# MIDI.net
KiCad netlist of a schematic drawn in Altium Designer
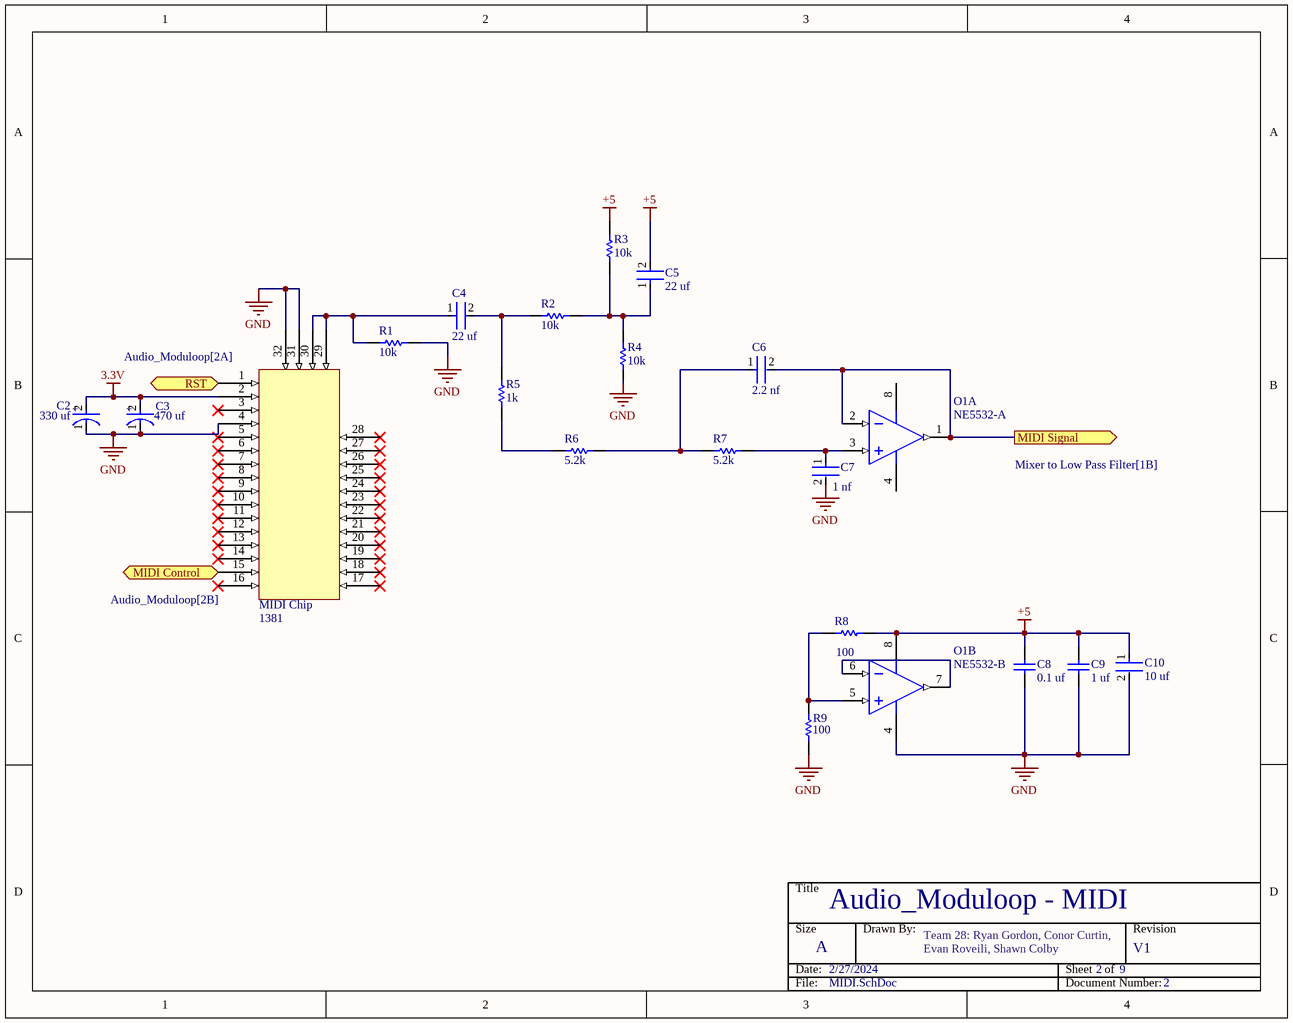
[diagram p0: MIDI.SchDoc]

(export (version "E")
  (design (tool "Eeschema 10.0.6"))
  (components
    (comp (ref "C2")
      (value "330 uf")
      (footprint "FP-RAD-TH-D_6_3_0_5-L_11-MFG")
      (description "Aluminum Electrolytic Capacitors (Radial Lead Type) 330uF ±20% 6.3V")
      (fields (field (name "TOLERANCE") "20%"))
      (libsource (lib "Altium Content Vault") (part "a00bbbee19879c290e62620ae7e47b1"))
    )
    (comp (ref "C3")
      (value "470 uf")
      (footprint "FP-RAD-TH-D_10_0_5-L_16_1-MFG")
      (description "Aluminum Electrolytic Capacitors (Radial Lead Type) AEC-Q200 Qualified 470uF ±20% 25V")
      (fields (field (name "TOLERANCE") "20%") (field (name "VOLTAGE") "25V"))
      (libsource (lib "Altium Content Vault") (part "a00bbbee19879c290e62620ae7e47b1"))
    )
    (comp (ref "C4")
      (value "22 uf")
      (footprint "FP-RCEWM1-MFG")
      (description "CAP CER 22UF 25V X7R RADIAL")
      (fields (field (name "TOLERANCE") "20%"))
      (libsource (lib "Altium Content Vault") (part "02cd4be3c70576c341d710602a673aa"))
    )
    (comp (ref "C5")
      (value "22 uf")
      (footprint "FP-RCEWM1-MFG")
      (description "CAP CER 22UF 25V X7R RADIAL")
      (fields (field (name "TOLERANCE") "20%"))
      (libsource (lib "Altium Content Vault") (part "02cd4be3c70576c341d710602a673aa"))
    )
    (comp (ref "C6")
      (value "2.2 nf")
      (footprint "FP-RCE0DB-MFG")
      (description "Cap Ceramic 1nF 50V X7R ±10% Radial 2.5mm +125°C Ammo Pack")
      (fields (field (name "TOLERANCE") "10%"))
      (libsource (lib "Altium Content Vault") (part "b4654b650e69147ec39a6b967a45e02"))
    )
    (comp (ref "C7")
      (value "1 nf")
      (footprint "FP-RCE0DB-MFG")
      (description "Cap Ceramic 470pF 100V X7R ±10% Radial 2.5mm +125°C Ammo Pack")
      (fields (field (name "TOLERANCE") "10%"))
      (libsource (lib "Altium Content Vault") (part "b4654b650e69147ec39a6b967a45e02"))
    )
    (comp (ref "C8")
      (value "0.1 uf")
      (footprint "CAPC2013X135X45ML10T25")
      (description "Chip Capacitor, 0.1 uF, +/- 10%, 50 V, -55 to 125 degC, 0805 (2012 Metric), RoHS, Tape and Reel")
      (fields (field (name "VOLTAGE") "50V") (field (name "TOLERANCE") "10%"))
      (libsource (lib "Altium Content Vault") (part "CAP-NP-2"))
    )
    (comp (ref "C9")
      (value "1 uf")
      (footprint "CAPC2013X145X50LL20T25")
      (fields (field (name "MANUFACTURER") "Kemet") (field (name "PART NUMBER") "C0805C105K4PACTU"))
      (libsource (lib "Altium Content Vault") (part "CAP"))
    )
    (comp (ref "C10")
      (value "10 uf")
      (footprint "FP-C0805C-DG-MFG")
      (description "CAP CER 10UF 10V X5R 0805")
      (fields (field (name "TOLERANCE") "10%") (field (name "MANUFACTURER PART NUMBER") "C0805C106K8PACTU"))
      (libsource (lib "Altium Content Vault") (part "11868f565c42a9108669ba33697ecf6"))
    )
    (comp (ref "MIDI Chip")
      (value "1381")
      (footprint "FEATHERWING")
      (description "Conn, Rect, PowerPoleHousing, PP180Series, Blue, 180A, 600V")
      (libsource (lib "Ryamgordon") (part "1381"))
    )
    (comp (ref "O1")
      (value "NE5532-A")
      (footprint "ONSC-SOIC-8-751-07_V")
      (fields (field (name "MANUFACTURER") "On Semiconductor") (field (name "PARTNUMBER") "NE5532AD8R2G"))
      (libsource (lib "Altium Content Vault") (part "ONSC-NE5532-SOIC-8-751-07"))
    )
    (comp (ref "R1")
      (value "10k")
      (footprint "RESC2013X60X35NL10T20")
      (description "Chip Resistor, 10 KOhm, +/- 1%, 0.125 W, -55 to 155 degC, 0805 (2012 Metric), RoHS, Tape and Reel")
      (fields (field (name "MANUFACTURER") "Yageo"))
      (libsource (lib "Altium Content Vault") (part "RES-2"))
    )
    (comp (ref "R2")
      (value "10k")
      (footprint "RESC2013X60X35NL10T20")
      (description "Chip Resistor, 10 KOhm, +/- 1%, 0.125 W, -55 to 155 degC, 0805 (2012 Metric), RoHS, Tape and Reel")
      (fields (field (name "MANUFACTURER") "Yageo"))
      (libsource (lib "Altium Content Vault") (part "RES-2"))
    )
    (comp (ref "R3")
      (value "10k")
      (footprint "RESC2013X60X35NL10T20")
      (description "Chip Resistor, 10 KOhm, +/- 1%, 0.125 W, -55 to 155 degC, 0805 (2012 Metric), RoHS, Tape and Reel")
      (fields (field (name "MANUFACTURER") "Yageo"))
      (libsource (lib "Altium Content Vault") (part "RES-2"))
    )
    (comp (ref "R4")
      (value "10k")
      (footprint "RESC2013X60X35NL10T20")
      (description "Chip Resistor, 10 KOhm, +/- 1%, 0.125 W, -55 to 155 degC, 0805 (2012 Metric), RoHS, Tape and Reel")
      (fields (field (name "MANUFACTURER") "Yageo"))
      (libsource (lib "Altium Content Vault") (part "RES-2"))
    )
    (comp (ref "R5")
      (value "1k")
      (footprint "RESC2013X60X40LL20T25")
      (fields (field (name "MANUFACTURER") "Panasonic") (field (name "PART NUMBER") "ERA6AEB152V"))
      (libsource (lib "Altium Content Vault") (part "RES"))
    )
    (comp (ref "R6")
      (value "5.2k")
      (footprint "RESC2013X70X40LL20T20")
      (fields (field (name "MANUFACTURER") "Panasonic") (field (name "PART NUMBER") "ERJ6ENF6801V"))
      (libsource (lib "Altium Content Vault") (part "RES"))
    )
    (comp (ref "R7")
      (value "5.2k")
      (footprint "RESC2013X70X40LL20T20")
      (fields (field (name "MANUFACTURER") "Panasonic") (field (name "PART NUMBER") "ERJ6ENF6801V"))
      (libsource (lib "Altium Content Vault") (part "RES"))
    )
    (comp (ref "R8")
      (value "100")
      (footprint "RESC2013X60X40ML20T25")
      (fields (field (name "MANUFACTURER") "Panasonic") (field (name "PART NUMBER") "ERA6AEB101V"))
      (libsource (lib "Altium Content Vault") (part "RES"))
    )
    (comp (ref "R9")
      (value "100")
      (footprint "RESC2013X60X40ML20T25")
      (fields (field (name "MANUFACTURER") "Panasonic") (field (name "PART NUMBER") "ERA6AEB101V"))
      (libsource (lib "Altium Content Vault") (part "RES"))
    )
  )
  (nets
    (net (code "1") (name "+5") (class "Default")
      (node (ref "C10") (pin "1") (pinfunction "1_1") (pintype "passive"))
      (node (ref "C5") (pin "2") (pinfunction "2_2") (pintype "passive"))
      (node (ref "C8") (pin "1") (pinfunction "1_1") (pintype "passive"))
      (node (ref "C9") (pin "1") (pinfunction "1_1") (pintype "passive"))
      (node (ref "O1") (pin "8") (pinfunction "V+_8") (pintype "power_in"))
      (node (ref "R3") (pin "1") (pinfunction "1_1") (pintype "passive"))
      (node (ref "R8") (pin "2") (pinfunction "2_2") (pintype "passive"))
    )
    (net (code "2") (name "/MIDI Control") (class "Default")
      (node (ref "MIDI Chip") (pin "15") (pintype "input"))
    )
    (net (code "3") (name "/MIDI Signal") (class "Default")
      (node (ref "C6") (pin "2") (pinfunction "2_2") (pintype "passive"))
      (node (ref "O1") (pin "1") (pinfunction "OUTA_1") (pintype "output"))
      (node (ref "O1") (pin "2") (pinfunction "INA-_2") (pintype "input"))
    )
    (net (code "4") (name "/RST") (class "Default") (node (ref "MIDI Chip") (pin "1") (pintype "input")))
    (net (code "5") (name "3.3V") (class "Default")
      (node (ref "C2") (pin "2") (pinfunction "A_2") (pintype "passive"))
      (node (ref "C3") (pin "2") (pinfunction "A_2") (pintype "passive"))
      (node (ref "MIDI Chip") (pin "2") (pintype "input"))
    )
    (net (code "6") (name "GND") (class "Default")
      (node (ref "C10") (pin "2") (pinfunction "2_2") (pintype "passive"))
      (node (ref "C2") (pin "1") (pinfunction "C_1") (pintype "passive"))
      (node (ref "C3") (pin "1") (pinfunction "C_1") (pintype "passive"))
      (node (ref "C7") (pin "2") (pinfunction "2_2") (pintype "passive"))
      (node (ref "C8") (pin "2") (pinfunction "2_2") (pintype "passive"))
      (node (ref "C9") (pin "2") (pinfunction "2_2") (pintype "passive"))
      (node (ref "MIDI Chip") (pin "31") (pintype "input"))
      (node (ref "MIDI Chip") (pin "32") (pintype "input"))
      (node (ref "MIDI Chip") (pin "4") (pintype "input"))
      (node (ref "O1") (pin "4") (pinfunction "V-_4") (pintype "power_in"))
      (node (ref "R1") (pin "2") (pinfunction "2_2") (pintype "passive"))
      (node (ref "R4") (pin "2") (pinfunction "2_2") (pintype "passive"))
      (node (ref "R9") (pin "1") (pinfunction "1_1") (pintype "passive"))
    )
    (net (code "7") (name "Net-(C4-Pad1)") (class "Default")
      (node (ref "C4") (pin "1") (pinfunction "1_1") (pintype "passive"))
      (node (ref "MIDI Chip") (pin "29") (pintype "input"))
      (node (ref "MIDI Chip") (pin "30") (pintype "input"))
      (node (ref "R1") (pin "1") (pinfunction "1_1") (pintype "passive"))
    )
    (net (code "8") (name "Net-(C4-Pad2)") (class "Default")
      (node (ref "C4") (pin "2") (pinfunction "2_2") (pintype "passive"))
      (node (ref "R2") (pin "1") (pinfunction "1_1") (pintype "passive"))
      (node (ref "R5") (pin "2") (pinfunction "2_2") (pintype "passive"))
    )
    (net (code "9") (name "Net-(C5-Pad1)") (class "Default")
      (node (ref "C5") (pin "1") (pinfunction "1_1") (pintype "passive"))
      (node (ref "R2") (pin "2") (pinfunction "2_2") (pintype "passive"))
      (node (ref "R3") (pin "2") (pinfunction "2_2") (pintype "passive"))
      (node (ref "R4") (pin "1") (pinfunction "1_1") (pintype "passive"))
    )
    (net (code "10") (name "Net-(C6-Pad1)") (class "Default")
      (node (ref "C6") (pin "1") (pinfunction "1_1") (pintype "passive"))
      (node (ref "R6") (pin "2") (pinfunction "2_2") (pintype "passive"))
      (node (ref "R7") (pin "1") (pinfunction "1_1") (pintype "passive"))
    )
    (net (code "11") (name "Net-(O1A-INA+)") (class "Default")
      (node (ref "C7") (pin "1") (pinfunction "1_1") (pintype "passive"))
      (node (ref "O1") (pin "3") (pinfunction "INA+_3") (pintype "input"))
      (node (ref "R7") (pin "2") (pinfunction "2_2") (pintype "passive"))
    )
    (net (code "12") (name "Net-(O1B-INB+)") (class "Default")
      (node (ref "O1") (pin "5") (pinfunction "INB+_5") (pintype "input"))
      (node (ref "R8") (pin "1") (pinfunction "1_1") (pintype "passive"))
      (node (ref "R9") (pin "2") (pinfunction "2_2") (pintype "passive"))
    )
    (net (code "13") (name "Net-(O1B-INB-)") (class "Default")
      (node (ref "O1") (pin "6") (pinfunction "INB-_6") (pintype "input"))
      (node (ref "O1") (pin "7") (pinfunction "OUTB_7") (pintype "output"))
    )
    (net (code "14") (name "Net-(R5-Pad1)") (class "Default")
      (node (ref "R5") (pin "1") (pinfunction "1_1") (pintype "passive"))
      (node (ref "R6") (pin "1") (pinfunction "1_1") (pintype "passive"))
    )
    (net (code "15") (name "unconnected-(MIDI Chip-Pad3)") (class "Default")
      (node (ref "MIDI Chip") (pin "3") (pintype "input+no_connect"))
    )
    (net (code "16") (name "unconnected-(MIDI Chip-Pad5)") (class "Default")
      (node (ref "MIDI Chip") (pin "5") (pintype "input+no_connect"))
    )
    (net (code "17") (name "unconnected-(MIDI Chip-Pad6)") (class "Default")
      (node (ref "MIDI Chip") (pin "6") (pintype "input+no_connect"))
    )
    (net (code "18") (name "unconnected-(MIDI Chip-Pad7)") (class "Default")
      (node (ref "MIDI Chip") (pin "7") (pintype "input+no_connect"))
    )
    (net (code "19") (name "unconnected-(MIDI Chip-Pad8)") (class "Default")
      (node (ref "MIDI Chip") (pin "8") (pintype "input+no_connect"))
    )
    (net (code "20") (name "unconnected-(MIDI Chip-Pad9)") (class "Default")
      (node (ref "MIDI Chip") (pin "9") (pintype "input+no_connect"))
    )
    (net (code "21") (name "unconnected-(MIDI Chip-Pad10)") (class "Default")
      (node (ref "MIDI Chip") (pin "10") (pintype "input+no_connect"))
    )
    (net (code "22") (name "unconnected-(MIDI Chip-Pad11)") (class "Default")
      (node (ref "MIDI Chip") (pin "11") (pintype "input+no_connect"))
    )
    (net (code "23") (name "unconnected-(MIDI Chip-Pad12)") (class "Default")
      (node (ref "MIDI Chip") (pin "12") (pintype "input+no_connect"))
    )
    (net (code "24") (name "unconnected-(MIDI Chip-Pad13)") (class "Default")
      (node (ref "MIDI Chip") (pin "13") (pintype "input+no_connect"))
    )
    (net (code "25") (name "unconnected-(MIDI Chip-Pad14)") (class "Default")
      (node (ref "MIDI Chip") (pin "14") (pintype "input+no_connect"))
    )
    (net (code "26") (name "unconnected-(MIDI Chip-Pad16)") (class "Default")
      (node (ref "MIDI Chip") (pin "16") (pintype "input+no_connect"))
    )
    (net (code "27") (name "unconnected-(MIDI Chip-Pad17)") (class "Default")
      (node (ref "MIDI Chip") (pin "17") (pintype "input+no_connect"))
    )
    (net (code "28") (name "unconnected-(MIDI Chip-Pad18)") (class "Default")
      (node (ref "MIDI Chip") (pin "18") (pintype "input+no_connect"))
    )
    (net (code "29") (name "unconnected-(MIDI Chip-Pad19)") (class "Default")
      (node (ref "MIDI Chip") (pin "19") (pintype "input+no_connect"))
    )
    (net (code "30") (name "unconnected-(MIDI Chip-Pad20)") (class "Default")
      (node (ref "MIDI Chip") (pin "20") (pintype "input+no_connect"))
    )
    (net (code "31") (name "unconnected-(MIDI Chip-Pad21)") (class "Default")
      (node (ref "MIDI Chip") (pin "21") (pintype "input+no_connect"))
    )
    (net (code "32") (name "unconnected-(MIDI Chip-Pad22)") (class "Default")
      (node (ref "MIDI Chip") (pin "22") (pintype "input+no_connect"))
    )
    (net (code "33") (name "unconnected-(MIDI Chip-Pad23)") (class "Default")
      (node (ref "MIDI Chip") (pin "23") (pintype "input+no_connect"))
    )
    (net (code "34") (name "unconnected-(MIDI Chip-Pad24)") (class "Default")
      (node (ref "MIDI Chip") (pin "24") (pintype "input+no_connect"))
    )
    (net (code "35") (name "unconnected-(MIDI Chip-Pad25)") (class "Default")
      (node (ref "MIDI Chip") (pin "25") (pintype "input+no_connect"))
    )
    (net (code "36") (name "unconnected-(MIDI Chip-Pad26)") (class "Default")
      (node (ref "MIDI Chip") (pin "26") (pintype "input+no_connect"))
    )
    (net (code "37") (name "unconnected-(MIDI Chip-Pad27)") (class "Default")
      (node (ref "MIDI Chip") (pin "27") (pintype "input+no_connect"))
    )
    (net (code "38") (name "unconnected-(MIDI Chip-Pad28)") (class "Default")
      (node (ref "MIDI Chip") (pin "28") (pintype "input+no_connect"))
    )
    (net (code "39") (name "unconnected-(O1A-V+-Pad8)") (class "Default")
      (node (ref "O1") (pin "8") (pinfunction "V+_8") (pintype "power_in"))
    )
    (net (code "40") (name "unconnected-(O1A-V--Pad4)") (class "Default")
      (node (ref "O1") (pin "4") (pinfunction "V-_4") (pintype "power_in"))
    )
  )
)
